# layer4.net
KiCad netlist of a schematic drawn in EAGLE
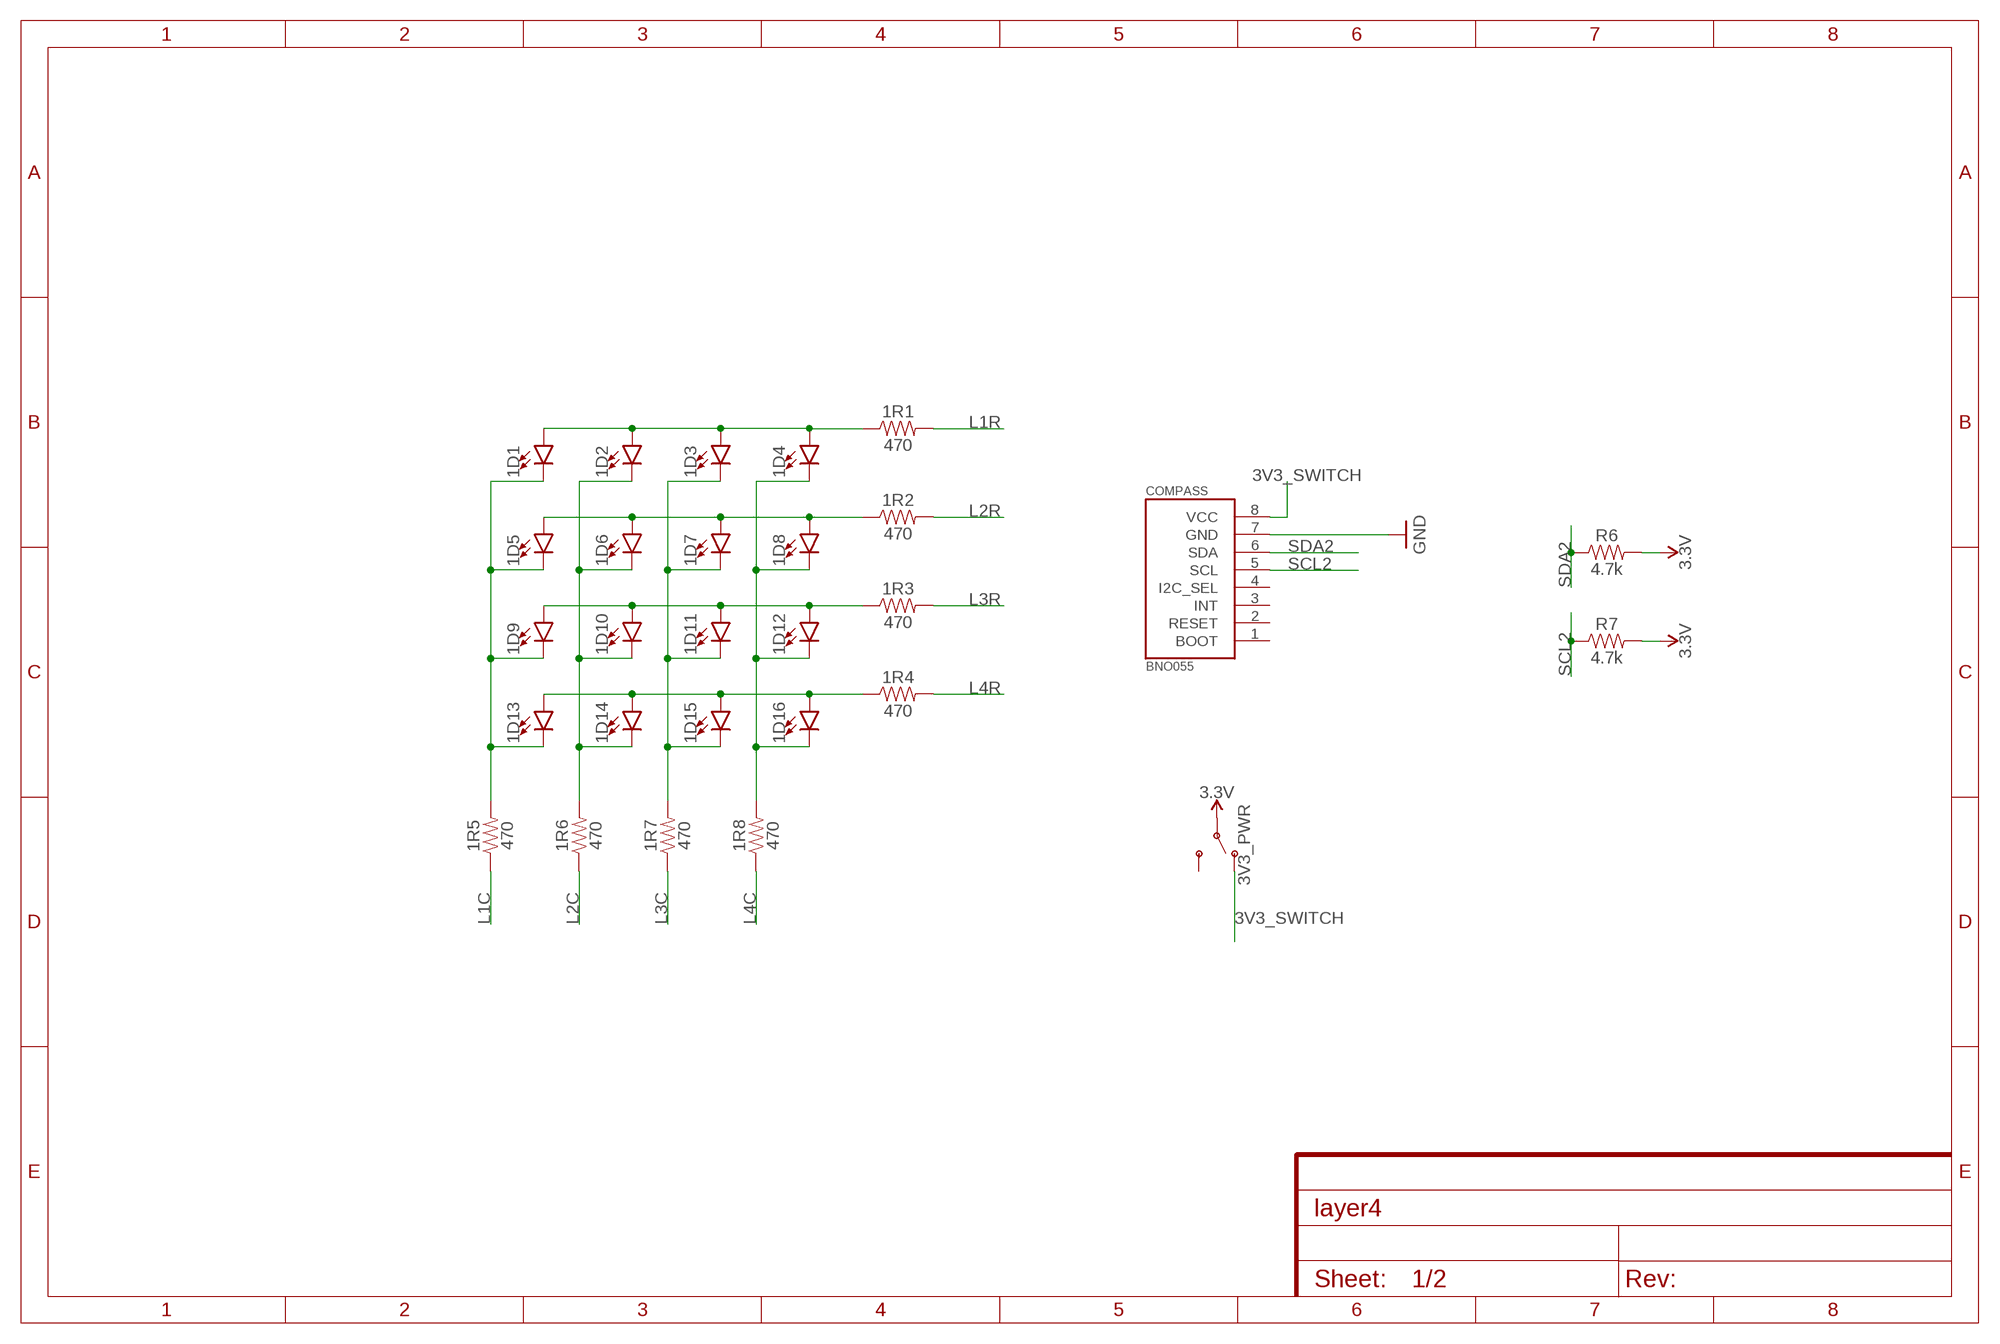
[diagram p0: schematic, sheet 1]
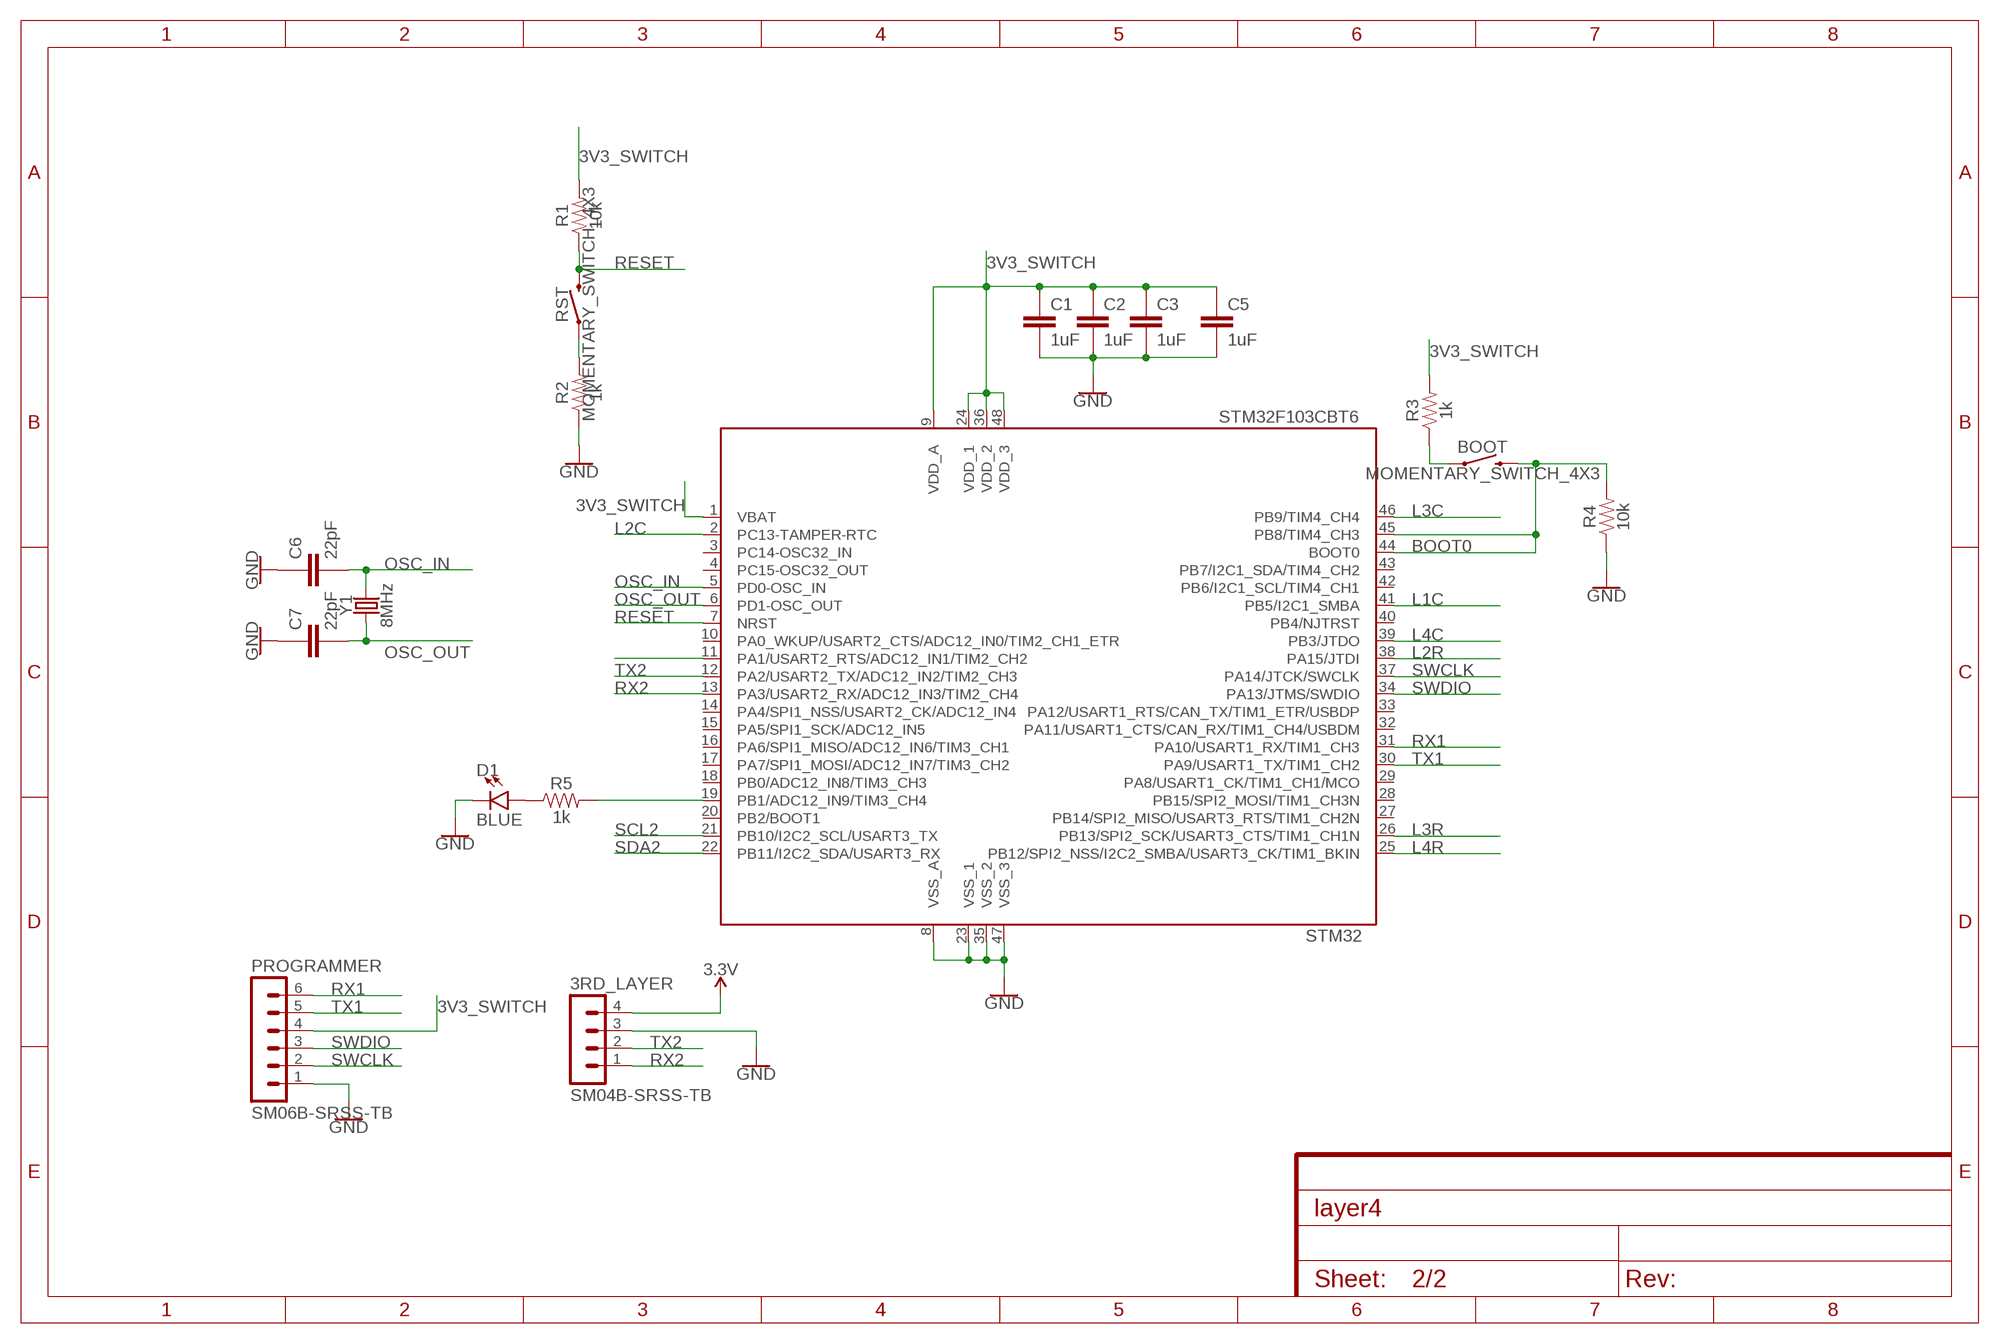
[diagram p1: schematic, sheet 2]

(export (version "E")
  (design (tool "Eeschema 10.0.6"))
  (components
    (comp (ref "1D1")
      (value "LED0603")
      (footprint "eagle-import:LED-0603")
      (libsource (lib "eagle-import") (part "LED0603"))
    )
    (comp (ref "1D2")
      (value "LED0603")
      (footprint "eagle-import:LED-0603")
      (libsource (lib "eagle-import") (part "LED0603"))
    )
    (comp (ref "1D3")
      (value "LED0603")
      (footprint "eagle-import:LED-0603")
      (libsource (lib "eagle-import") (part "LED0603"))
    )
    (comp (ref "1D4")
      (value "LED0603")
      (footprint "eagle-import:LED-0603")
      (libsource (lib "eagle-import") (part "LED0603"))
    )
    (comp (ref "1D5")
      (value "LED0603")
      (footprint "eagle-import:LED-0603")
      (libsource (lib "eagle-import") (part "LED0603"))
    )
    (comp (ref "1D6")
      (value "LED0603")
      (footprint "eagle-import:LED-0603")
      (libsource (lib "eagle-import") (part "LED0603"))
    )
    (comp (ref "1D7")
      (value "LED0603")
      (footprint "eagle-import:LED-0603")
      (libsource (lib "eagle-import") (part "LED0603"))
    )
    (comp (ref "1D8")
      (value "LED0603")
      (footprint "eagle-import:LED-0603")
      (libsource (lib "eagle-import") (part "LED0603"))
    )
    (comp (ref "1D9")
      (value "LED0603")
      (footprint "eagle-import:LED-0603")
      (libsource (lib "eagle-import") (part "LED0603"))
    )
    (comp (ref "1D10")
      (value "LED0603")
      (footprint "eagle-import:LED-0603")
      (libsource (lib "eagle-import") (part "LED0603"))
    )
    (comp (ref "1D11")
      (value "LED0603")
      (footprint "eagle-import:LED-0603")
      (libsource (lib "eagle-import") (part "LED0603"))
    )
    (comp (ref "1D12")
      (value "LED0603")
      (footprint "eagle-import:LED-0603")
      (libsource (lib "eagle-import") (part "LED0603"))
    )
    (comp (ref "1D13")
      (value "LED0603")
      (footprint "eagle-import:LED-0603")
      (libsource (lib "eagle-import") (part "LED0603"))
    )
    (comp (ref "1D14")
      (value "LED0603")
      (footprint "eagle-import:LED-0603")
      (libsource (lib "eagle-import") (part "LED0603"))
    )
    (comp (ref "1D15")
      (value "LED0603")
      (footprint "eagle-import:LED-0603")
      (libsource (lib "eagle-import") (part "LED0603"))
    )
    (comp (ref "1D16")
      (value "LED0603")
      (footprint "eagle-import:LED-0603")
      (libsource (lib "eagle-import") (part "LED0603"))
    )
    (comp (ref "1R1")
      (value "470")
      (footprint "eagle-import:R0603")
      (libsource (lib "eagle-import") (part "RESISTOR0603"))
    )
    (comp (ref "1R2")
      (value "470")
      (footprint "eagle-import:R0603")
      (libsource (lib "eagle-import") (part "RESISTOR0603"))
    )
    (comp (ref "1R3")
      (value "470")
      (footprint "eagle-import:R0603")
      (libsource (lib "eagle-import") (part "RESISTOR0603"))
    )
    (comp (ref "1R4")
      (value "470")
      (footprint "eagle-import:R0603")
      (libsource (lib "eagle-import") (part "RESISTOR0603"))
    )
    (comp (ref "1R5")
      (value "470")
      (footprint "eagle-import:R0603")
      (libsource (lib "eagle-import") (part "RESISTOR0603"))
    )
    (comp (ref "1R6")
      (value "470")
      (footprint "eagle-import:R0603")
      (libsource (lib "eagle-import") (part "RESISTOR0603"))
    )
    (comp (ref "1R7")
      (value "470")
      (footprint "eagle-import:R0603")
      (libsource (lib "eagle-import") (part "RESISTOR0603"))
    )
    (comp (ref "1R8")
      (value "470")
      (footprint "eagle-import:R0603")
      (libsource (lib "eagle-import") (part "RESISTOR0603"))
    )
    (comp (ref "3V3_PWR")
      (value "SWITCH-SPDT-PTH-11.6X4.0MM-LOCK")
      (footprint "eagle-import:SWITCH_SPDT_PTH_11.6X4.0MM_LOCK")
      (libsource (lib "eagle-import") (part "SWITCH-SPDT-PTH-11.6X4.0MM-LOCK"))
    )
    (comp (ref "COMPASS")
      (value "BNO055")
      (footprint "eagle-import:BNO055")
      (libsource (lib "eagle-import") (part "BNO055"))
    )
    (comp (ref "R6")
      (value "4.7k")
      (footprint "eagle-import:0603")
      (libsource (lib "eagle-import") (part "4.7KOHM-0603-1/10W-1%"))
    )
    (comp (ref "R7")
      (value "4.7k")
      (footprint "eagle-import:0603")
      (libsource (lib "eagle-import") (part "4.7KOHM-0603-1/10W-1%"))
    )
    (comp (ref "3RD_LAYER")
      (value "SM04B-SRSS-TB")
      (footprint "eagle-import:SM04B-SRSS-TB")
      (libsource (lib "eagle-import") (part "SM04B-SRSS-TB"))
    )
    (comp (ref "BOOT")
      (value "MOMENTARY_SWITCH_4X3")
      (footprint "eagle-import:MOMENTARY_SWITCH_4X3")
      (libsource (lib "eagle-import") (part "MOMENTARY_SWITCH_4X3"))
    )
    (comp (ref "C1")
      (value "1uF")
      (footprint "eagle-import:C0603")
      (libsource (lib "eagle-import") (part "CAPACITOR0603"))
    )
    (comp (ref "C2")
      (value "1uF")
      (footprint "eagle-import:C0603")
      (libsource (lib "eagle-import") (part "CAPACITOR0603"))
    )
    (comp (ref "C3")
      (value "1uF")
      (footprint "eagle-import:C0603")
      (libsource (lib "eagle-import") (part "CAPACITOR0603"))
    )
    (comp (ref "C5")
      (value "1uF")
      (footprint "eagle-import:C0603")
      (libsource (lib "eagle-import") (part "CAPACITOR0603"))
    )
    (comp (ref "C6")
      (value "22pF")
      (footprint "eagle-import:C0603")
      (libsource (lib "eagle-import") (part "CAPACITOR0603"))
    )
    (comp (ref "C7")
      (value "22pF")
      (footprint "eagle-import:C0603")
      (libsource (lib "eagle-import") (part "CAPACITOR0603"))
    )
    (comp (ref "D1")
      (value "BLUE")
      (footprint "eagle-import:LED-0603")
      (libsource (lib "eagle-import") (part "LED0603"))
    )
    (comp (ref "PROGRAMMER")
      (value "SM06B-SRSS-TB")
      (footprint "eagle-import:SM06B-SRSS-TB")
      (libsource (lib "eagle-import") (part "SM06B-SRSS-TB"))
    )
    (comp (ref "R1")
      (value "10k")
      (footprint "eagle-import:R0603")
      (libsource (lib "eagle-import") (part "RESISTOR0603"))
    )
    (comp (ref "R2")
      (value "1k")
      (footprint "eagle-import:R0603")
      (libsource (lib "eagle-import") (part "RESISTOR0603"))
    )
    (comp (ref "R3")
      (value "1k")
      (footprint "eagle-import:R0603")
      (libsource (lib "eagle-import") (part "RESISTOR0603"))
    )
    (comp (ref "R4")
      (value "10k")
      (footprint "eagle-import:R0603")
      (libsource (lib "eagle-import") (part "RESISTOR0603"))
    )
    (comp (ref "R5")
      (value "1k")
      (footprint "eagle-import:R0603")
      (libsource (lib "eagle-import") (part "RESISTOR0603"))
    )
    (comp (ref "RST")
      (value "MOMENTARY_SWITCH_4X3")
      (footprint "eagle-import:MOMENTARY_SWITCH_4X3")
      (libsource (lib "eagle-import") (part "MOMENTARY_SWITCH_4X3"))
    )
    (comp (ref "STM32")
      (value "STM32F103CBT6")
      (footprint "eagle-import:LQFP48")
      (libsource (lib "eagle-import") (part "STM32F103CBT6"))
    )
    (comp (ref "Y1")
      (value "8MHz")
      (footprint "eagle-import:CRYSTAL-SMD-5X3.2-2PAD")
      (libsource (lib "eagle-import") (part "CRYSTALSMD-5X3.2-2PAD"))
    )
  )
  (nets
    (net (code "1") (name "3.3V") (class "Default")
      (node (ref "3RD_LAYER") (pin "4") (pinfunction "4_4") (pintype "passive"))
      (node (ref "3V3_PWR") (pin "2") (pinfunction "P_2") (pintype "passive"))
      (node (ref "R6") (pin "2") (pinfunction "2_2") (pintype "passive"))
      (node (ref "R7") (pin "2") (pinfunction "2_2") (pintype "passive"))
    )
    (net (code "2") (name "3V3_SWITCH") (class "Default")
      (node (ref "3V3_PWR") (pin "1") (pinfunction "O_1") (pintype "passive"))
      (node (ref "C1") (pin "1") (pinfunction "1_1") (pintype "passive"))
      (node (ref "C2") (pin "1") (pinfunction "1_1") (pintype "passive"))
      (node (ref "C3") (pin "1") (pinfunction "1_1") (pintype "passive"))
      (node (ref "C5") (pin "2") (pinfunction "2_2") (pintype "passive"))
      (node (ref "COMPASS") (pin "8") (pinfunction "VCC_8") (pintype "bidirectional"))
      (node (ref "PROGRAMMER") (pin "4") (pinfunction "4_4") (pintype "passive"))
      (node (ref "R1") (pin "2") (pinfunction "2_2") (pintype "passive"))
      (node (ref "R3") (pin "2") (pinfunction "2_2") (pintype "passive"))
      (node (ref "STM32") (pin "1") (pinfunction "VBAT_1") (pintype "power_in"))
      (node (ref "STM32") (pin "24") (pinfunction "VDD_1_24") (pintype "power_in"))
      (node (ref "STM32") (pin "36") (pinfunction "VDD_2_36") (pintype "power_in"))
      (node (ref "STM32") (pin "48") (pinfunction "VDD_3_48") (pintype "power_in"))
      (node (ref "STM32") (pin "9") (pinfunction "VDD_A_9") (pintype "power_in"))
    )
    (net (code "3") (name "BOOT0") (class "Default")
      (node (ref "BOOT") (pin "P$2") (pinfunction "2_P$2") (pintype "passive"))
      (node (ref "R4") (pin "2") (pinfunction "2_2") (pintype "passive"))
      (node (ref "STM32") (pin "44") (pinfunction "BOOT0_44") (pintype "input"))
      (node (ref "STM32") (pin "45") (pinfunction "PB8/TIM4_CH3_45") (pintype "bidirectional"))
    )
    (net (code "4") (name "GND") (class "Default")
      (node (ref "3RD_LAYER") (pin "3") (pinfunction "3_3") (pintype "passive"))
      (node (ref "C1") (pin "2") (pinfunction "2_2") (pintype "passive"))
      (node (ref "C2") (pin "2") (pinfunction "2_2") (pintype "passive"))
      (node (ref "C3") (pin "2") (pinfunction "2_2") (pintype "passive"))
      (node (ref "C5") (pin "1") (pinfunction "1_1") (pintype "passive"))
      (node (ref "C6") (pin "1") (pinfunction "1_1") (pintype "passive"))
      (node (ref "C7") (pin "1") (pinfunction "1_1") (pintype "passive"))
      (node (ref "COMPASS") (pin "7") (pinfunction "GND_7") (pintype "bidirectional"))
      (node (ref "D1") (pin "C") (pinfunction "C_C") (pintype "passive"))
      (node (ref "PROGRAMMER") (pin "1") (pinfunction "1_1") (pintype "passive"))
      (node (ref "R2") (pin "1") (pinfunction "1_1") (pintype "passive"))
      (node (ref "R4") (pin "1") (pinfunction "1_1") (pintype "passive"))
      (node (ref "STM32") (pin "23") (pinfunction "VSS_1_23") (pintype "power_in"))
      (node (ref "STM32") (pin "35") (pinfunction "VSS_2_35") (pintype "power_in"))
      (node (ref "STM32") (pin "47") (pinfunction "VSS_3_47") (pintype "power_in"))
      (node (ref "STM32") (pin "8") (pinfunction "VSS_A_8") (pintype "power_in"))
    )
    (net (code "5") (name "L1C") (class "Default")
      (node (ref "1R5") (pin "1") (pinfunction "1_1") (pintype "passive"))
      (node (ref "STM32") (pin "41") (pinfunction "PB5/I2C1_SMBA_41") (pintype "input"))
    )
    (net (code "6") (name "L1R") (class "Default")
      (node (ref "1R1") (pin "2") (pinfunction "2_2") (pintype "passive"))
      (node (ref "STM32") (pin "11") (pinfunction "PA1/USART2_RTS/ADC12_IN1/TIM2_CH2_11") (pintype "bidirectional"))
    )
    (net (code "7") (name "L2C") (class "Default")
      (node (ref "1R6") (pin "1") (pinfunction "1_1") (pintype "passive"))
      (node (ref "STM32") (pin "2") (pinfunction "PC13-TAMPER-RTC_2") (pintype "input"))
    )
    (net (code "8") (name "L2R") (class "Default")
      (node (ref "1R2") (pin "2") (pinfunction "2_2") (pintype "passive"))
      (node (ref "STM32") (pin "38") (pinfunction "PA15/JTDI_38") (pintype "bidirectional"))
    )
    (net (code "9") (name "L3C") (class "Default")
      (node (ref "1R7") (pin "1") (pinfunction "1_1") (pintype "passive"))
      (node (ref "STM32") (pin "46") (pinfunction "PB9/TIM4_CH4_46") (pintype "input"))
    )
    (net (code "10") (name "L3R") (class "Default")
      (node (ref "1R3") (pin "2") (pinfunction "2_2") (pintype "passive"))
      (node (ref "STM32") (pin "26") (pinfunction "PB13/SPI2_SCK/USART3_CTS/TIM1_CH1N_26") (pintype "input"))
    )
    (net (code "11") (name "L4C") (class "Default")
      (node (ref "1R8") (pin "1") (pinfunction "1_1") (pintype "passive"))
      (node (ref "STM32") (pin "39") (pinfunction "PB3/JTDO_39") (pintype "bidirectional"))
    )
    (net (code "12") (name "L4R") (class "Default")
      (node (ref "1R4") (pin "2") (pinfunction "2_2") (pintype "passive"))
      (node (ref "STM32") (pin "25") (pinfunction "PB12/SPI2_NSS/I2C2_SMBA/USART3_CK/TIM1_BKIN_25") (pintype "input"))
    )
    (net (code "13") (name "Net-(1D1-PadA)") (class "Default")
      (node (ref "1D1") (pin "A") (pinfunction "A_A") (pintype "passive"))
      (node (ref "1D2") (pin "A") (pinfunction "A_A") (pintype "passive"))
      (node (ref "1D3") (pin "A") (pinfunction "A_A") (pintype "passive"))
      (node (ref "1D4") (pin "A") (pinfunction "A_A") (pintype "passive"))
      (node (ref "1R1") (pin "1") (pinfunction "1_1") (pintype "passive"))
    )
    (net (code "14") (name "Net-(1D1-PadC)") (class "Default")
      (node (ref "1D1") (pin "C") (pinfunction "C_C") (pintype "passive"))
      (node (ref "1D13") (pin "C") (pinfunction "C_C") (pintype "passive"))
      (node (ref "1D5") (pin "C") (pinfunction "C_C") (pintype "passive"))
      (node (ref "1D9") (pin "C") (pinfunction "C_C") (pintype "passive"))
      (node (ref "1R5") (pin "2") (pinfunction "2_2") (pintype "passive"))
    )
    (net (code "15") (name "Net-(1D5-PadA)") (class "Default")
      (node (ref "1D5") (pin "A") (pinfunction "A_A") (pintype "passive"))
      (node (ref "1D6") (pin "A") (pinfunction "A_A") (pintype "passive"))
      (node (ref "1D7") (pin "A") (pinfunction "A_A") (pintype "passive"))
      (node (ref "1D8") (pin "A") (pinfunction "A_A") (pintype "passive"))
      (node (ref "1R2") (pin "1") (pinfunction "1_1") (pintype "passive"))
    )
    (net (code "16") (name "Net-(1D10-PadA)") (class "Default")
      (node (ref "1D10") (pin "A") (pinfunction "A_A") (pintype "passive"))
      (node (ref "1D11") (pin "A") (pinfunction "A_A") (pintype "passive"))
      (node (ref "1D12") (pin "A") (pinfunction "A_A") (pintype "passive"))
      (node (ref "1D9") (pin "A") (pinfunction "A_A") (pintype "passive"))
      (node (ref "1R3") (pin "1") (pinfunction "1_1") (pintype "passive"))
    )
    (net (code "17") (name "Net-(1D10-PadC)") (class "Default")
      (node (ref "1D10") (pin "C") (pinfunction "C_C") (pintype "passive"))
      (node (ref "1D14") (pin "C") (pinfunction "C_C") (pintype "passive"))
      (node (ref "1D2") (pin "C") (pinfunction "C_C") (pintype "passive"))
      (node (ref "1D6") (pin "C") (pinfunction "C_C") (pintype "passive"))
      (node (ref "1R6") (pin "2") (pinfunction "2_2") (pintype "passive"))
    )
    (net (code "18") (name "Net-(1D11-PadC)") (class "Default")
      (node (ref "1D11") (pin "C") (pinfunction "C_C") (pintype "passive"))
      (node (ref "1D15") (pin "C") (pinfunction "C_C") (pintype "passive"))
      (node (ref "1D3") (pin "C") (pinfunction "C_C") (pintype "passive"))
      (node (ref "1D7") (pin "C") (pinfunction "C_C") (pintype "passive"))
      (node (ref "1R7") (pin "2") (pinfunction "2_2") (pintype "passive"))
    )
    (net (code "19") (name "Net-(1D12-PadC)") (class "Default")
      (node (ref "1D12") (pin "C") (pinfunction "C_C") (pintype "passive"))
      (node (ref "1D16") (pin "C") (pinfunction "C_C") (pintype "passive"))
      (node (ref "1D4") (pin "C") (pinfunction "C_C") (pintype "passive"))
      (node (ref "1D8") (pin "C") (pinfunction "C_C") (pintype "passive"))
      (node (ref "1R8") (pin "2") (pinfunction "2_2") (pintype "passive"))
    )
    (net (code "20") (name "Net-(1D13-PadA)") (class "Default")
      (node (ref "1D13") (pin "A") (pinfunction "A_A") (pintype "passive"))
      (node (ref "1D14") (pin "A") (pinfunction "A_A") (pintype "passive"))
      (node (ref "1D15") (pin "A") (pinfunction "A_A") (pintype "passive"))
      (node (ref "1D16") (pin "A") (pinfunction "A_A") (pintype "passive"))
      (node (ref "1R4") (pin "1") (pinfunction "1_1") (pintype "passive"))
    )
    (net (code "21") (name "Net-(BOOT-1)") (class "Default")
      (node (ref "BOOT") (pin "P$1") (pinfunction "1_P$1") (pintype "passive"))
      (node (ref "R3") (pin "1") (pinfunction "1_1") (pintype "passive"))
    )
    (net (code "22") (name "Net-(D1-PadA)") (class "Default")
      (node (ref "D1") (pin "A") (pinfunction "A_A") (pintype "passive"))
      (node (ref "R5") (pin "1") (pinfunction "1_1") (pintype "passive"))
    )
    (net (code "23") (name "Net-(RST-1)") (class "Default")
      (node (ref "R2") (pin "2") (pinfunction "2_2") (pintype "passive"))
      (node (ref "RST") (pin "P$1") (pinfunction "1_P$1") (pintype "passive"))
    )
    (net (code "24") (name "Net-(STM32-PB1{slash}ADC12_IN9{slash}TIM3_CH4)") (class "Default")
      (node (ref "R5") (pin "2") (pinfunction "2_2") (pintype "passive"))
      (node (ref "STM32") (pin "19") (pinfunction "PB1/ADC12_IN9/TIM3_CH4_19") (pintype "bidirectional"))
    )
    (net (code "25") (name "OSC_IN") (class "Default")
      (node (ref "C6") (pin "2") (pinfunction "2_2") (pintype "passive"))
      (node (ref "STM32") (pin "5") (pinfunction "PD0-OSC_IN_5") (pintype "input"))
      (node (ref "Y1") (pin "P$2") (pinfunction "2_P$2") (pintype "passive"))
    )
    (net (code "26") (name "OSC_OUT") (class "Default")
      (node (ref "C7") (pin "2") (pinfunction "2_2") (pintype "passive"))
      (node (ref "STM32") (pin "6") (pinfunction "PD1-OSC_OUT_6") (pintype "input"))
      (node (ref "Y1") (pin "P$1") (pinfunction "1_P$1") (pintype "passive"))
    )
    (net (code "27") (name "RESET") (class "Default")
      (node (ref "R1") (pin "1") (pinfunction "1_1") (pintype "passive"))
      (node (ref "RST") (pin "P$2") (pinfunction "2_P$2") (pintype "passive"))
      (node (ref "STM32") (pin "7") (pinfunction "NRST_7") (pintype "input"))
    )
    (net (code "28") (name "RX1") (class "Default")
      (node (ref "PROGRAMMER") (pin "6") (pinfunction "6_6") (pintype "passive"))
      (node (ref "STM32") (pin "31") (pinfunction "PA10/USART1_RX/TIM1_CH3_31") (pintype "bidirectional"))
    )
    (net (code "29") (name "RX2") (class "Default")
      (node (ref "3RD_LAYER") (pin "1") (pinfunction "1_1") (pintype "passive"))
      (node (ref "STM32") (pin "13") (pinfunction "PA3/USART2_RX/ADC12_IN3/TIM2_CH4_13") (pintype "bidirectional"))
    )
    (net (code "30") (name "SCL2") (class "Default")
      (node (ref "COMPASS") (pin "5") (pinfunction "SCL_5") (pintype "bidirectional"))
      (node (ref "R7") (pin "1") (pinfunction "1_1") (pintype "passive"))
      (node (ref "STM32") (pin "21") (pinfunction "PB10/I2C2_SCL/USART3_TX_21") (pintype "input"))
    )
    (net (code "31") (name "SDA2") (class "Default")
      (node (ref "COMPASS") (pin "6") (pinfunction "SDA_6") (pintype "bidirectional"))
      (node (ref "R6") (pin "1") (pinfunction "1_1") (pintype "passive"))
      (node (ref "STM32") (pin "22") (pinfunction "PB11/I2C2_SDA/USART3_RX_22") (pintype "input"))
    )
    (net (code "32") (name "SWCLK") (class "Default")
      (node (ref "PROGRAMMER") (pin "2") (pinfunction "2_2") (pintype "passive"))
      (node (ref "STM32") (pin "37") (pinfunction "PA14/JTCK/SWCLK_37") (pintype "bidirectional"))
    )
    (net (code "33") (name "SWDIO") (class "Default")
      (node (ref "PROGRAMMER") (pin "3") (pinfunction "3_3") (pintype "passive"))
      (node (ref "STM32") (pin "34") (pinfunction "PA13/JTMS/SWDIO_34") (pintype "bidirectional"))
    )
    (net (code "34") (name "TX1") (class "Default")
      (node (ref "PROGRAMMER") (pin "5") (pinfunction "5_5") (pintype "passive"))
      (node (ref "STM32") (pin "30") (pinfunction "PA9/USART1_TX/TIM1_CH2_30") (pintype "input"))
    )
    (net (code "35") (name "TX2") (class "Default")
      (node (ref "3RD_LAYER") (pin "2") (pinfunction "2_2") (pintype "passive"))
      (node (ref "STM32") (pin "12") (pinfunction "PA2/USART2_TX/ADC12_IN2/TIM2_CH3_12") (pintype "bidirectional"))
    )
    (net (code "36") (name "unconnected-(3V3_PWR-S-Pad3)") (class "Default")
      (node (ref "3V3_PWR") (pin "3") (pinfunction "S_3") (pintype "passive"))
    )
    (net (code "37") (name "unconnected-(COMPASS-BOOT-Pad1)") (class "Default")
      (node (ref "COMPASS") (pin "1") (pinfunction "BOOT_1") (pintype "bidirectional"))
    )
    (net (code "38") (name "unconnected-(COMPASS-I2C_SEL-Pad4)") (class "Default")
      (node (ref "COMPASS") (pin "4") (pinfunction "I2C_SEL_4") (pintype "bidirectional"))
    )
    (net (code "39") (name "unconnected-(COMPASS-INT-Pad3)") (class "Default")
      (node (ref "COMPASS") (pin "3") (pinfunction "INT_3") (pintype "bidirectional"))
    )
    (net (code "40") (name "unconnected-(COMPASS-RESET-Pad2)") (class "Default")
      (node (ref "COMPASS") (pin "2") (pinfunction "RESET_2") (pintype "bidirectional"))
    )
    (net (code "41") (name "unconnected-(STM32-PA0_WKUP{slash}USART2_CTS{slash}ADC12_IN0{slash}TIM2_CH1_ETR-Pad10)") (class "Default")
      (node (ref "STM32") (pin "10") (pinfunction "PA0_WKUP/USART2_CTS/ADC12_IN0/TIM2_CH1_ETR_10") (pintype "bidirectional"))
    )
    (net (code "42") (name "unconnected-(STM32-PA4{slash}SPI1_NSS{slash}USART2_CK{slash}ADC12_IN4-Pad14)") (class "Default")
      (node (ref "STM32") (pin "14") (pinfunction "PA4/SPI1_NSS/USART2_CK/ADC12_IN4_14") (pintype "bidirectional"))
    )
    (net (code "43") (name "unconnected-(STM32-PA5{slash}SPI1_SCK{slash}ADC12_IN5-Pad15)") (class "Default")
      (node (ref "STM32") (pin "15") (pinfunction "PA5/SPI1_SCK/ADC12_IN5_15") (pintype "bidirectional"))
    )
    (net (code "44") (name "unconnected-(STM32-PA6{slash}SPI1_MISO{slash}ADC12_IN6{slash}TIM3_CH1-Pad16)") (class "Default")
      (node (ref "STM32") (pin "16") (pinfunction "PA6/SPI1_MISO/ADC12_IN6/TIM3_CH1_16") (pintype "bidirectional"))
    )
    (net (code "45") (name "unconnected-(STM32-PA7{slash}SPI1_MOSI{slash}ADC12_IN7{slash}TIM3_CH2-Pad17)") (class "Default")
      (node (ref "STM32") (pin "17") (pinfunction "PA7/SPI1_MOSI/ADC12_IN7/TIM3_CH2_17") (pintype "bidirectional"))
    )
    (net (code "46") (name "unconnected-(STM32-PA8{slash}USART1_CK{slash}TIM1_CH1{slash}MCO-Pad29)") (class "Default")
      (node (ref "STM32") (pin "29") (pinfunction "PA8/USART1_CK/TIM1_CH1/MCO_29") (pintype "bidirectional"))
    )
    (net (code "47") (name "unconnected-(STM32-PA11{slash}USART1_CTS{slash}CAN_RX{slash}TIM1_CH4{slash}USBDM-Pad32)") (class "Default")
      (node (ref "STM32") (pin "32") (pinfunction "PA11/USART1_CTS/CAN_RX/TIM1_CH4/USBDM_32") (pintype "bidirectional"))
    )
    (net (code "48") (name "unconnected-(STM32-PA12{slash}USART1_RTS{slash}CAN_TX{slash}TIM1_ETR{slash}USBDP-Pad33)") (class "Default")
      (node (ref "STM32") (pin "33") (pinfunction "PA12/USART1_RTS/CAN_TX/TIM1_ETR/USBDP_33") (pintype "bidirectional"))
    )
    (net (code "49") (name "unconnected-(STM32-PB0{slash}ADC12_IN8{slash}TIM3_CH3-Pad18)") (class "Default")
      (node (ref "STM32") (pin "18") (pinfunction "PB0/ADC12_IN8/TIM3_CH3_18") (pintype "bidirectional"))
    )
    (net (code "50") (name "unconnected-(STM32-PB2{slash}BOOT1-Pad20)") (class "Default")
      (node (ref "STM32") (pin "20") (pinfunction "PB2/BOOT1_20") (pintype "bidirectional"))
    )
    (net (code "51") (name "unconnected-(STM32-PB4{slash}NJTRST-Pad40)") (class "Default")
      (node (ref "STM32") (pin "40") (pinfunction "PB4/NJTRST_40") (pintype "bidirectional"))
    )
    (net (code "52") (name "unconnected-(STM32-PB6{slash}I2C1_SCL{slash}TIM4_CH1-Pad42)") (class "Default")
      (node (ref "STM32") (pin "42") (pinfunction "PB6/I2C1_SCL/TIM4_CH1_42") (pintype "input"))
    )
    (net (code "53") (name "unconnected-(STM32-PB7{slash}I2C1_SDA{slash}TIM4_CH2-Pad43)") (class "Default")
      (node (ref "STM32") (pin "43") (pinfunction "PB7/I2C1_SDA/TIM4_CH2_43") (pintype "bidirectional"))
    )
    (net (code "54") (name "unconnected-(STM32-PB14{slash}SPI2_MISO{slash}USART3_RTS{slash}TIM1_CH2N-Pad27)") (class "Default")
      (node (ref "STM32") (pin "27") (pinfunction "PB14/SPI2_MISO/USART3_RTS/TIM1_CH2N_27") (pintype "input"))
    )
    (net (code "55") (name "unconnected-(STM32-PB15{slash}SPI2_MOSI{slash}TIM1_CH3N-Pad28)") (class "Default")
      (node (ref "STM32") (pin "28") (pinfunction "PB15/SPI2_MOSI/TIM1_CH3N_28") (pintype "input"))
    )
    (net (code "56") (name "unconnected-(STM32-PC14-OSC32_IN-Pad3)") (class "Default")
      (node (ref "STM32") (pin "3") (pinfunction "PC14-OSC32_IN_3") (pintype "input"))
    )
    (net (code "57") (name "unconnected-(STM32-PC15-OSC32_OUT-Pad4)") (class "Default")
      (node (ref "STM32") (pin "4") (pinfunction "PC15-OSC32_OUT_4") (pintype "input"))
    )
  )
)
